# chaves.net
KiCad netlist of a schematic drawn in EAGLE
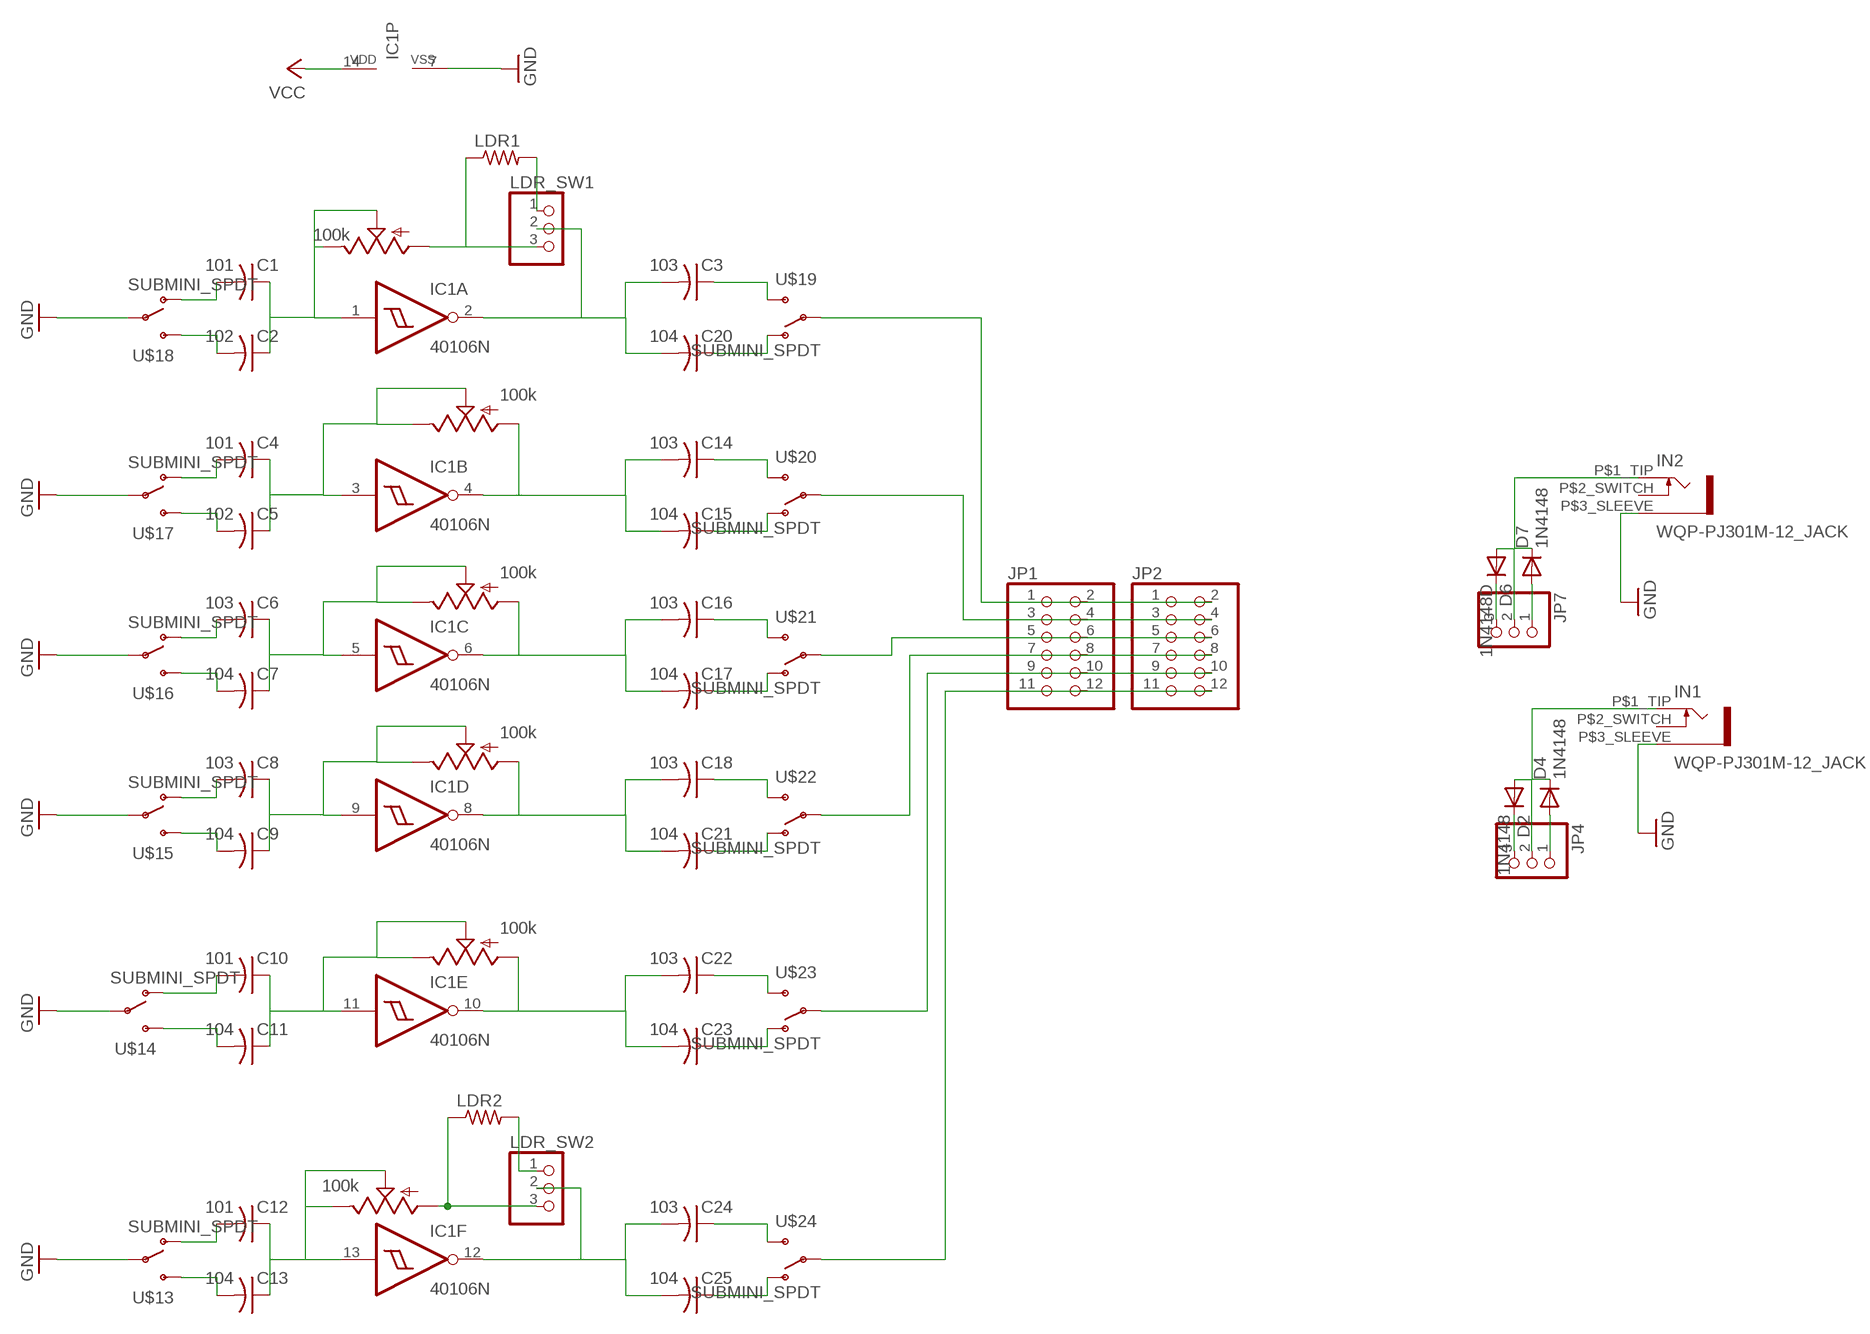
[diagram p0: schematic, sheet 1]
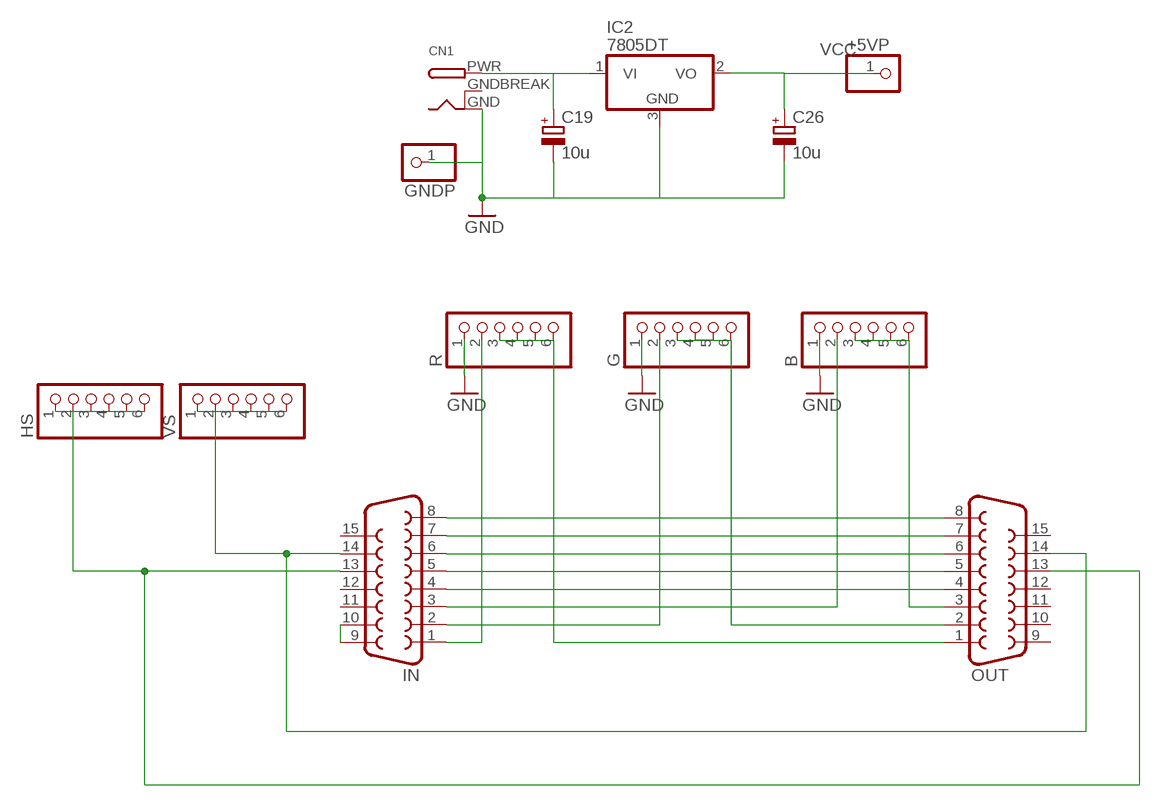
[diagram p1: schematic, sheet 2]

(export (version "E")
  (design (tool "Eeschema 10.0.6"))
  (components
    (comp (ref "+5VP")
      (value "PINHD-1X1CB")
      (footprint "eagle-import:1X01-CLEANBIG")
      (libsource (lib "eagle-import") (part "PINHD-1X1CB"))
    )
    (comp (ref "B")
      (value "PINHD-1X6CLEAN")
      (footprint "eagle-import:1X06-CLEAN")
      (libsource (lib "eagle-import") (part "PINHD-1X6CLEAN"))
    )
    (comp (ref "C19")
      (value "10u")
      (footprint "eagle-import:E2,5-5")
      (libsource (lib "eagle-import") (part "CPOL-EUE2.5-5"))
    )
    (comp (ref "C26")
      (value "10u")
      (footprint "eagle-import:E2,5-5")
      (libsource (lib "eagle-import") (part "CPOL-EUE2.5-5"))
    )
    (comp (ref "CN1")
      (value "DCBARRELPTH")
      (footprint "eagle-import:DCJACK_2MM_PTH")
      (libsource (lib "eagle-import") (part "DCBARRELPTH"))
    )
    (comp (ref "G")
      (value "PINHD-1X6CLEAN")
      (footprint "eagle-import:1X06-CLEAN")
      (libsource (lib "eagle-import") (part "PINHD-1X6CLEAN"))
    )
    (comp (ref "GNDP")
      (value "PINHD-1X1CB")
      (footprint "eagle-import:1X01-CLEANBIG")
      (libsource (lib "eagle-import") (part "PINHD-1X1CB"))
    )
    (comp (ref "HS")
      (value "PINHD-1X6CLEAN")
      (footprint "eagle-import:1X06-CLEAN")
      (libsource (lib "eagle-import") (part "PINHD-1X6CLEAN"))
    )
    (comp (ref "IC2")
      (value "7805DT")
      (footprint "eagle-import:TO252")
      (libsource (lib "eagle-import") (part "78DT05"))
    )
    (comp (ref "IN")
      (value "F15HDH")
      (footprint "eagle-import:HDF15H")
      (libsource (lib "eagle-import") (part "F15HDH"))
    )
    (comp (ref "OUT")
      (value "F15HDH")
      (footprint "eagle-import:HDF15H")
      (libsource (lib "eagle-import") (part "F15HDH"))
    )
    (comp (ref "R")
      (value "PINHD-1X6CLEAN")
      (footprint "eagle-import:1X06-CLEAN")
      (libsource (lib "eagle-import") (part "PINHD-1X6CLEAN"))
    )
    (comp (ref "VS")
      (value "PINHD-1X6CLEAN")
      (footprint "eagle-import:1X06-CLEAN")
      (libsource (lib "eagle-import") (part "PINHD-1X6CLEAN"))
    )
    (comp (ref "C1")
      (value "101")
      (footprint "eagle-import:C050-025X075")
      (libsource (lib "eagle-import") (part "C-US050-025X075"))
    )
    (comp (ref "C2")
      (value "102")
      (footprint "eagle-import:C050-025X075")
      (libsource (lib "eagle-import") (part "C-US050-025X075"))
    )
    (comp (ref "C3")
      (value "103")
      (footprint "eagle-import:C050-025X075")
      (libsource (lib "eagle-import") (part "C-US050-025X075"))
    )
    (comp (ref "C4")
      (value "101")
      (footprint "eagle-import:C050-025X075")
      (libsource (lib "eagle-import") (part "C-US050-025X075"))
    )
    (comp (ref "C5")
      (value "102")
      (footprint "eagle-import:C050-025X075")
      (libsource (lib "eagle-import") (part "C-US050-025X075"))
    )
    (comp (ref "C6")
      (value "103")
      (footprint "eagle-import:C050-025X075")
      (libsource (lib "eagle-import") (part "C-US050-025X075"))
    )
    (comp (ref "C7")
      (value "104")
      (footprint "eagle-import:C050-025X075")
      (libsource (lib "eagle-import") (part "C-US050-025X075"))
    )
    (comp (ref "C8")
      (value "103")
      (footprint "eagle-import:C050-025X075")
      (libsource (lib "eagle-import") (part "C-US050-025X075"))
    )
    (comp (ref "C9")
      (value "104")
      (footprint "eagle-import:C050-025X075")
      (libsource (lib "eagle-import") (part "C-US050-025X075"))
    )
    (comp (ref "C10")
      (value "101")
      (footprint "eagle-import:C050-025X075")
      (libsource (lib "eagle-import") (part "C-US050-025X075"))
    )
    (comp (ref "C11")
      (value "104")
      (footprint "eagle-import:C050-025X075")
      (libsource (lib "eagle-import") (part "C-US050-025X075"))
    )
    (comp (ref "C12")
      (value "101")
      (footprint "eagle-import:C050-025X075")
      (libsource (lib "eagle-import") (part "C-US050-025X075"))
    )
    (comp (ref "C13")
      (value "104")
      (footprint "eagle-import:C050-025X075")
      (libsource (lib "eagle-import") (part "C-US050-025X075"))
    )
    (comp (ref "C14")
      (value "103")
      (footprint "eagle-import:C050-025X075")
      (libsource (lib "eagle-import") (part "C-US050-025X075"))
    )
    (comp (ref "C15")
      (value "104")
      (footprint "eagle-import:C050-025X075")
      (libsource (lib "eagle-import") (part "C-US050-025X075"))
    )
    (comp (ref "C16")
      (value "103")
      (footprint "eagle-import:C050-025X075")
      (libsource (lib "eagle-import") (part "C-US050-025X075"))
    )
    (comp (ref "C17")
      (value "104")
      (footprint "eagle-import:C050-025X075")
      (libsource (lib "eagle-import") (part "C-US050-025X075"))
    )
    (comp (ref "C18")
      (value "103")
      (footprint "eagle-import:C050-025X075")
      (libsource (lib "eagle-import") (part "C-US050-025X075"))
    )
    (comp (ref "C20")
      (value "104")
      (footprint "eagle-import:C050-025X075")
      (libsource (lib "eagle-import") (part "C-US050-025X075"))
    )
    (comp (ref "C21")
      (value "104")
      (footprint "eagle-import:C050-025X075")
      (libsource (lib "eagle-import") (part "C-US050-025X075"))
    )
    (comp (ref "C22")
      (value "103")
      (footprint "eagle-import:C050-025X075")
      (libsource (lib "eagle-import") (part "C-US050-025X075"))
    )
    (comp (ref "C23")
      (value "104")
      (footprint "eagle-import:C050-025X075")
      (libsource (lib "eagle-import") (part "C-US050-025X075"))
    )
    (comp (ref "C24")
      (value "103")
      (footprint "eagle-import:C050-025X075")
      (libsource (lib "eagle-import") (part "C-US050-025X075"))
    )
    (comp (ref "C25")
      (value "104")
      (footprint "eagle-import:C050-025X075")
      (libsource (lib "eagle-import") (part "C-US050-025X075"))
    )
    (comp (ref "D2")
      (value "1N4148")
      (footprint "eagle-import:DO35-7")
      (libsource (lib "eagle-import") (part "1N4148DO35-7"))
    )
    (comp (ref "D4")
      (value "1N4148")
      (footprint "eagle-import:DO35-7")
      (libsource (lib "eagle-import") (part "1N4148DO35-7"))
    )
    (comp (ref "D6")
      (value "1N4148D")
      (footprint "eagle-import:DO35-7")
      (libsource (lib "eagle-import") (part "1N4148DO35-7"))
    )
    (comp (ref "D7")
      (value "1N4148")
      (footprint "eagle-import:DO35-7")
      (libsource (lib "eagle-import") (part "1N4148DO35-7"))
    )
    (comp (ref "IC1")
      (value "40106N")
      (footprint "eagle-import:DIL14")
      (libsource (lib "eagle-import") (part "40106N"))
    )
    (comp (ref "IN1")
      (value "WQP-PJ301M-12_JACK")
      (footprint "eagle-import:WQP-PJ301M-12_JACK")
      (libsource (lib "eagle-import") (part "WQP-PJ301M-12_JACK"))
    )
    (comp (ref "IN2")
      (value "WQP-PJ301M-12_JACK")
      (footprint "eagle-import:WQP-PJ301M-12_JACK")
      (libsource (lib "eagle-import") (part "WQP-PJ301M-12_JACK"))
    )
    (comp (ref "JP1")
      (value "PINHD-2X6")
      (footprint "eagle-import:2X06")
      (libsource (lib "eagle-import") (part "PINHD-2X6"))
    )
    (comp (ref "JP2")
      (value "PINHD-2X6")
      (footprint "eagle-import:2X06")
      (libsource (lib "eagle-import") (part "PINHD-2X6"))
    )
    (comp (ref "JP4")
      (value "PINHD-1X3CB")
      (footprint "eagle-import:1X03-CLEANBIG")
      (libsource (lib "eagle-import") (part "PINHD-1X3CB"))
    )
    (comp (ref "JP7")
      (value "PINHD-1X3CB")
      (footprint "eagle-import:1X03-CLEANBIG")
      (libsource (lib "eagle-import") (part "PINHD-1X3CB"))
    )
    (comp (ref "LDR1")
      (value "R-US_0204/7")
      (footprint "eagle-import:0204_7")
      (libsource (lib "eagle-import") (part "R-US_0204/7"))
    )
    (comp (ref "LDR2")
      (value "R-US_0204/7")
      (footprint "eagle-import:0204_7")
      (libsource (lib "eagle-import") (part "R-US_0204/7"))
    )
    (comp (ref "LDR_SW1")
      (value "PINHD-1X3")
      (footprint "eagle-import:1X03")
      (libsource (lib "eagle-import") (part "pinhead_PINHD-1X3"))
    )
    (comp (ref "LDR_SW2")
      (value "PINHD-1X3")
      (footprint "eagle-import:1X03")
      (libsource (lib "eagle-import") (part "pinhead_PINHD-1X3"))
    )
    (comp (ref "POT1")
      (value "100k")
      (footprint "eagle-import:ALPS_POT_VERTICAL")
      (libsource (lib "eagle-import") (part "POT_USVERTICAL"))
    )
    (comp (ref "POT2")
      (value "100k")
      (footprint "eagle-import:ALPS_POT_VERTICAL")
      (libsource (lib "eagle-import") (part "POT_USVERTICAL"))
    )
    (comp (ref "POT3")
      (value "100k")
      (footprint "eagle-import:ALPS_POT_VERTICAL")
      (libsource (lib "eagle-import") (part "POT_USVERTICAL"))
    )
    (comp (ref "POT4")
      (value "100k")
      (footprint "eagle-import:ALPS_POT_VERTICAL")
      (libsource (lib "eagle-import") (part "POT_USVERTICAL"))
    )
    (comp (ref "POT5")
      (value "100k")
      (footprint "eagle-import:ALPS_POT_VERTICAL")
      (libsource (lib "eagle-import") (part "POT_USVERTICAL"))
    )
    (comp (ref "POT6")
      (value "100k")
      (footprint "eagle-import:ALPS_POT_VERTICAL")
      (libsource (lib "eagle-import") (part "POT_USVERTICAL"))
    )
    (comp (ref "U$13")
      (value "SUBMINI_SPDT")
      (footprint "eagle-import:SUBMINI_TOGGLE")
      (libsource (lib "eagle-import") (part "SUBMINI_SPDT"))
    )
    (comp (ref "U$14")
      (value "SUBMINI_SPDT")
      (footprint "eagle-import:SUBMINI_TOGGLE")
      (libsource (lib "eagle-import") (part "SUBMINI_SPDT"))
    )
    (comp (ref "U$15")
      (value "SUBMINI_SPDT")
      (footprint "eagle-import:SUBMINI_TOGGLE")
      (libsource (lib "eagle-import") (part "SUBMINI_SPDT"))
    )
    (comp (ref "U$16")
      (value "SUBMINI_SPDT")
      (footprint "eagle-import:SUBMINI_TOGGLE")
      (libsource (lib "eagle-import") (part "SUBMINI_SPDT"))
    )
    (comp (ref "U$17")
      (value "SUBMINI_SPDT")
      (footprint "eagle-import:SUBMINI_TOGGLE")
      (libsource (lib "eagle-import") (part "SUBMINI_SPDT"))
    )
    (comp (ref "U$18")
      (value "SUBMINI_SPDT")
      (footprint "eagle-import:SUBMINI_TOGGLE")
      (libsource (lib "eagle-import") (part "SUBMINI_SPDT"))
    )
    (comp (ref "U$19")
      (value "SUBMINI_SPDT")
      (footprint "eagle-import:SUBMINI_TOGGLE")
      (libsource (lib "eagle-import") (part "SUBMINI_SPDT"))
    )
    (comp (ref "U$20")
      (value "SUBMINI_SPDT")
      (footprint "eagle-import:SUBMINI_TOGGLE")
      (libsource (lib "eagle-import") (part "SUBMINI_SPDT"))
    )
    (comp (ref "U$21")
      (value "SUBMINI_SPDT")
      (footprint "eagle-import:SUBMINI_TOGGLE")
      (libsource (lib "eagle-import") (part "SUBMINI_SPDT"))
    )
    (comp (ref "U$22")
      (value "SUBMINI_SPDT")
      (footprint "eagle-import:SUBMINI_TOGGLE")
      (libsource (lib "eagle-import") (part "SUBMINI_SPDT"))
    )
    (comp (ref "U$23")
      (value "SUBMINI_SPDT")
      (footprint "eagle-import:SUBMINI_TOGGLE")
      (libsource (lib "eagle-import") (part "SUBMINI_SPDT"))
    )
    (comp (ref "U$24")
      (value "SUBMINI_SPDT")
      (footprint "eagle-import:SUBMINI_TOGGLE")
      (libsource (lib "eagle-import") (part "SUBMINI_SPDT"))
    )
  )
  (nets
    (net (code "1") (name "GND") (class "Default")
      (node (ref "B") (pin "1") (pinfunction "1_1") (pintype "passive"))
      (node (ref "C19") (pin "-") (pinfunction "-_-") (pintype "passive"))
      (node (ref "C26") (pin "-") (pinfunction "-_-") (pintype "passive"))
      (node (ref "CN1") (pin "GND") (pinfunction "GND_GND") (pintype "power_in"))
      (node (ref "G") (pin "1") (pinfunction "1_1") (pintype "passive"))
      (node (ref "GNDP") (pin "1") (pinfunction "1_1") (pintype "passive"))
      (node (ref "IC1") (pin "7") (pinfunction "VSS_7") (pintype "power_in"))
      (node (ref "IC2") (pin "3") (pinfunction "GND_3") (pintype "passive"))
      (node (ref "IN") (pin "10") (pinfunction "10_10") (pintype "passive"))
      (node (ref "IN") (pin "4") (pinfunction "4_4") (pintype "passive"))
      (node (ref "IN") (pin "5") (pinfunction "5_5") (pintype "passive"))
      (node (ref "IN") (pin "6") (pinfunction "6_6") (pintype "passive"))
      (node (ref "IN") (pin "7") (pinfunction "7_7") (pintype "passive"))
      (node (ref "IN") (pin "8") (pinfunction "8_8") (pintype "passive"))
      (node (ref "IN") (pin "9") (pinfunction "9_9") (pintype "passive"))
      (node (ref "IN1") (pin "P$3_SLEEVE") (pinfunction "1_P$3_SLEEVE") (pintype "passive"))
      (node (ref "IN2") (pin "P$3_SLEEVE") (pinfunction "1_P$3_SLEEVE") (pintype "passive"))
      (node (ref "OUT") (pin "4") (pinfunction "4_4") (pintype "passive"))
      (node (ref "OUT") (pin "5") (pinfunction "5_5") (pintype "passive"))
      (node (ref "OUT") (pin "6") (pinfunction "6_6") (pintype "passive"))
      (node (ref "OUT") (pin "7") (pinfunction "7_7") (pintype "passive"))
      (node (ref "OUT") (pin "8") (pinfunction "8_8") (pintype "passive"))
      (node (ref "R") (pin "1") (pinfunction "1_1") (pintype "passive"))
      (node (ref "U$13") (pin "COM") (pinfunction "COMMON_COM") (pintype "passive"))
      (node (ref "U$14") (pin "COM") (pinfunction "COMMON_COM") (pintype "passive"))
      (node (ref "U$15") (pin "COM") (pinfunction "COMMON_COM") (pintype "passive"))
      (node (ref "U$16") (pin "COM") (pinfunction "COMMON_COM") (pintype "passive"))
      (node (ref "U$17") (pin "COM") (pinfunction "COMMON_COM") (pintype "passive"))
      (node (ref "U$18") (pin "COM") (pinfunction "COMMON_COM") (pintype "passive"))
    )
    (net (code "2") (name "GNDBREAK") (class "Default")
      (node (ref "CN1") (pin "GNDBREAK") (pinfunction "GNDBREAK_GNDBREAK") (pintype "power_in"))
    )
    (net (code "3") (name "Net-(B-Pad2)") (class "Default")
      (node (ref "B") (pin "2") (pinfunction "2_2") (pintype "passive"))
      (node (ref "IN") (pin "3") (pinfunction "3_3") (pintype "passive"))
    )
    (net (code "4") (name "Net-(B-Pad3)") (class "Default")
      (node (ref "B") (pin "3") (pinfunction "3_3") (pintype "passive"))
      (node (ref "B") (pin "4") (pinfunction "4_4") (pintype "passive"))
      (node (ref "B") (pin "5") (pinfunction "5_5") (pintype "passive"))
      (node (ref "B") (pin "6") (pinfunction "6_6") (pintype "passive"))
      (node (ref "OUT") (pin "3") (pinfunction "3_3") (pintype "passive"))
    )
    (net (code "5") (name "Net-(D2-PadC)") (class "Default")
      (node (ref "D2") (pin "C") (pinfunction "C_C") (pintype "passive"))
      (node (ref "JP4") (pin "3") (pinfunction "3_3") (pintype "passive"))
    )
    (net (code "6") (name "Net-(D4-PadA)") (class "Default")
      (node (ref "D4") (pin "A") (pinfunction "A_A") (pintype "passive"))
      (node (ref "JP4") (pin "1") (pinfunction "1_1") (pintype "passive"))
    )
    (net (code "7") (name "Net-(D6-PadC)") (class "Default")
      (node (ref "D6") (pin "C") (pinfunction "C_C") (pintype "passive"))
      (node (ref "JP7") (pin "3") (pinfunction "3_3") (pintype "passive"))
    )
    (net (code "8") (name "Net-(D7-PadA)") (class "Default")
      (node (ref "D7") (pin "A") (pinfunction "A_A") (pintype "passive"))
      (node (ref "JP7") (pin "1") (pinfunction "1_1") (pintype "passive"))
    )
    (net (code "9") (name "Net-(G-Pad2)") (class "Default")
      (node (ref "G") (pin "2") (pinfunction "2_2") (pintype "passive"))
      (node (ref "IN") (pin "2") (pinfunction "2_2") (pintype "passive"))
    )
    (net (code "10") (name "Net-(G-Pad3)") (class "Default")
      (node (ref "G") (pin "3") (pinfunction "3_3") (pintype "passive"))
      (node (ref "G") (pin "4") (pinfunction "4_4") (pintype "passive"))
      (node (ref "G") (pin "5") (pinfunction "5_5") (pintype "passive"))
      (node (ref "G") (pin "6") (pinfunction "6_6") (pintype "passive"))
      (node (ref "OUT") (pin "2") (pinfunction "2_2") (pintype "passive"))
    )
    (net (code "11") (name "Net-(HS-Pad1)") (class "Default")
      (node (ref "HS") (pin "1") (pinfunction "1_1") (pintype "passive"))
      (node (ref "HS") (pin "2") (pinfunction "2_2") (pintype "passive"))
      (node (ref "HS") (pin "3") (pinfunction "3_3") (pintype "passive"))
      (node (ref "HS") (pin "4") (pinfunction "4_4") (pintype "passive"))
      (node (ref "HS") (pin "5") (pinfunction "5_5") (pintype "passive"))
      (node (ref "HS") (pin "6") (pinfunction "6_6") (pintype "passive"))
      (node (ref "IN") (pin "13") (pinfunction "13_13") (pintype "passive"))
      (node (ref "OUT") (pin "13") (pinfunction "13_13") (pintype "passive"))
    )
    (net (code "12") (name "Net-(IC1A-I)") (class "Default")
      (node (ref "C1") (pin "1") (pinfunction "1_1") (pintype "passive"))
      (node (ref "C2") (pin "1") (pinfunction "1_1") (pintype "passive"))
      (node (ref "IC1") (pin "1") (pinfunction "I_1") (pintype "input"))
      (node (ref "POT1") (pin "P$1") (pinfunction "E_P$1") (pintype "passive"))
      (node (ref "POT1") (pin "P$2") (pinfunction "S_P$2") (pintype "passive"))
    )
    (net (code "13") (name "Net-(IC1A-O)") (class "Default")
      (node (ref "C20") (pin "2") (pinfunction "2_2") (pintype "passive"))
      (node (ref "C3") (pin "2") (pinfunction "2_2") (pintype "passive"))
      (node (ref "IC1") (pin "2") (pinfunction "O_2") (pintype "output"))
      (node (ref "LDR_SW1") (pin "2") (pinfunction "2_2") (pintype "passive"))
    )
    (net (code "14") (name "Net-(IC1B-I)") (class "Default")
      (node (ref "C4") (pin "1") (pinfunction "1_1") (pintype "passive"))
      (node (ref "C5") (pin "1") (pinfunction "1_1") (pintype "passive"))
      (node (ref "IC1") (pin "3") (pinfunction "I_3") (pintype "input"))
      (node (ref "POT2") (pin "P$1") (pinfunction "E_P$1") (pintype "passive"))
      (node (ref "POT2") (pin "P$2") (pinfunction "S_P$2") (pintype "passive"))
    )
    (net (code "15") (name "Net-(IC1B-O)") (class "Default")
      (node (ref "C14") (pin "2") (pinfunction "2_2") (pintype "passive"))
      (node (ref "C15") (pin "2") (pinfunction "2_2") (pintype "passive"))
      (node (ref "IC1") (pin "4") (pinfunction "O_4") (pintype "output"))
      (node (ref "POT2") (pin "P$3") (pinfunction "A_P$3") (pintype "passive"))
    )
    (net (code "16") (name "Net-(IC1C-I)") (class "Default")
      (node (ref "C6") (pin "1") (pinfunction "1_1") (pintype "passive"))
      (node (ref "C7") (pin "1") (pinfunction "1_1") (pintype "passive"))
      (node (ref "IC1") (pin "5") (pinfunction "I_5") (pintype "input"))
      (node (ref "POT3") (pin "P$1") (pinfunction "E_P$1") (pintype "passive"))
      (node (ref "POT3") (pin "P$2") (pinfunction "S_P$2") (pintype "passive"))
    )
    (net (code "17") (name "Net-(IC1C-O)") (class "Default")
      (node (ref "C16") (pin "2") (pinfunction "2_2") (pintype "passive"))
      (node (ref "C17") (pin "2") (pinfunction "2_2") (pintype "passive"))
      (node (ref "IC1") (pin "6") (pinfunction "O_6") (pintype "output"))
      (node (ref "POT3") (pin "P$3") (pinfunction "A_P$3") (pintype "passive"))
    )
    (net (code "18") (name "Net-(IC1D-I)") (class "Default")
      (node (ref "C8") (pin "1") (pinfunction "1_1") (pintype "passive"))
      (node (ref "C9") (pin "1") (pinfunction "1_1") (pintype "passive"))
      (node (ref "IC1") (pin "9") (pinfunction "I_9") (pintype "input"))
      (node (ref "POT4") (pin "P$1") (pinfunction "E_P$1") (pintype "passive"))
      (node (ref "POT4") (pin "P$2") (pinfunction "S_P$2") (pintype "passive"))
    )
    (net (code "19") (name "Net-(IC1D-O)") (class "Default")
      (node (ref "C18") (pin "2") (pinfunction "2_2") (pintype "passive"))
      (node (ref "C21") (pin "2") (pinfunction "2_2") (pintype "passive"))
      (node (ref "IC1") (pin "8") (pinfunction "O_8") (pintype "output"))
      (node (ref "POT4") (pin "P$3") (pinfunction "A_P$3") (pintype "passive"))
    )
    (net (code "20") (name "Net-(IC1E-I)") (class "Default")
      (node (ref "C10") (pin "1") (pinfunction "1_1") (pintype "passive"))
      (node (ref "C11") (pin "1") (pinfunction "1_1") (pintype "passive"))
      (node (ref "IC1") (pin "11") (pinfunction "I_11") (pintype "input"))
      (node (ref "POT5") (pin "P$1") (pinfunction "E_P$1") (pintype "passive"))
      (node (ref "POT5") (pin "P$2") (pinfunction "S_P$2") (pintype "passive"))
    )
    (net (code "21") (name "Net-(IC1E-O)") (class "Default")
      (node (ref "C22") (pin "2") (pinfunction "2_2") (pintype "passive"))
      (node (ref "C23") (pin "2") (pinfunction "2_2") (pintype "passive"))
      (node (ref "IC1") (pin "10") (pinfunction "O_10") (pintype "output"))
      (node (ref "POT5") (pin "P$3") (pinfunction "A_P$3") (pintype "passive"))
    )
    (net (code "22") (name "Net-(IC1F-I)") (class "Default")
      (node (ref "C12") (pin "1") (pinfunction "1_1") (pintype "passive"))
      (node (ref "C13") (pin "1") (pinfunction "1_1") (pintype "passive"))
      (node (ref "IC1") (pin "13") (pinfunction "I_13") (pintype "input"))
      (node (ref "POT6") (pin "P$1") (pinfunction "E_P$1") (pintype "passive"))
      (node (ref "POT6") (pin "P$2") (pinfunction "S_P$2") (pintype "passive"))
    )
    (net (code "23") (name "Net-(IC1F-O)") (class "Default")
      (node (ref "C24") (pin "2") (pinfunction "2_2") (pintype "passive"))
      (node (ref "C25") (pin "2") (pinfunction "2_2") (pintype "passive"))
      (node (ref "IC1") (pin "12") (pinfunction "O_12") (pintype "output"))
      (node (ref "LDR_SW2") (pin "2") (pinfunction "2_2") (pintype "passive"))
    )
    (net (code "24") (name "Net-(IC2-VI)") (class "Default")
      (node (ref "C19") (pin "+") (pinfunction "+_+") (pintype "passive"))
      (node (ref "CN1") (pin "PWR") (pinfunction "PWR_PWR") (pintype "power_in"))
      (node (ref "IC2") (pin "1") (pinfunction "VI_1") (pintype "input"))
    )
    (net (code "25") (name "Net-(IN-Pad1)") (class "Default")
      (node (ref "IN") (pin "1") (pinfunction "1_1") (pintype "passive"))
      (node (ref "R") (pin "2") (pinfunction "2_2") (pintype "passive"))
    )
    (net (code "26") (name "Net-(IN-Pad14)") (class "Default")
      (node (ref "IN") (pin "14") (pinfunction "14_14") (pintype "passive"))
      (node (ref "OUT") (pin "14") (pinfunction "14_14") (pintype "passive"))
      (node (ref "VS") (pin "1") (pinfunction "1_1") (pintype "passive"))
      (node (ref "VS") (pin "2") (pinfunction "2_2") (pintype "passive"))
      (node (ref "VS") (pin "3") (pinfunction "3_3") (pintype "passive"))
      (node (ref "VS") (pin "4") (pinfunction "4_4") (pintype "passive"))
      (node (ref "VS") (pin "5") (pinfunction "5_5") (pintype "passive"))
      (node (ref "VS") (pin "6") (pinfunction "6_6") (pintype "passive"))
    )
    (net (code "27") (name "Net-(IN1-2)") (class "Default")
      (node (ref "D2") (pin "A") (pinfunction "A_A") (pintype "passive"))
      (node (ref "D4") (pin "C") (pinfunction "C_C") (pintype "passive"))
      (node (ref "IN1") (pin "P$1_TIP") (pinfunction "2_P$1_TIP") (pintype "passive"))
      (node (ref "JP4") (pin "2") (pinfunction "2_2") (pintype "passive"))
    )
    (net (code "28") (name "Net-(IN2-2)") (class "Default")
      (node (ref "D6") (pin "A") (pinfunction "A_A") (pintype "passive"))
      (node (ref "D7") (pin "C") (pinfunction "C_C") (pintype "passive"))
      (node (ref "IN2") (pin "P$1_TIP") (pinfunction "2_P$1_TIP") (pintype "passive"))
      (node (ref "JP7") (pin "2") (pinfunction "2_2") (pintype "passive"))
    )
    (net (code "29") (name "Net-(LDR1-Pad2)") (class "Default")
      (node (ref "LDR1") (pin "2") (pinfunction "2_2") (pintype "passive"))
      (node (ref "LDR_SW1") (pin "1") (pinfunction "1_1") (pintype "passive"))
    )
    (net (code "30") (name "Net-(LDR2-Pad2)") (class "Default")
      (node (ref "LDR2") (pin "2") (pinfunction "2_2") (pintype "passive"))
      (node (ref "LDR_SW2") (pin "1") (pinfunction "1_1") (pintype "passive"))
    )
    (net (code "31") (name "Net-(OUT-Pad1)") (class "Default")
      (node (ref "OUT") (pin "1") (pinfunction "1_1") (pintype "passive"))
      (node (ref "R") (pin "3") (pinfunction "3_3") (pintype "passive"))
      (node (ref "R") (pin "4") (pinfunction "4_4") (pintype "passive"))
      (node (ref "R") (pin "5") (pinfunction "5_5") (pintype "passive"))
      (node (ref "R") (pin "6") (pinfunction "6_6") (pintype "passive"))
    )
    (net (code "32") (name "Net-(POT1-A)") (class "Default")
      (node (ref "LDR1") (pin "1") (pinfunction "1_1") (pintype "passive"))
      (node (ref "LDR_SW1") (pin "3") (pinfunction "3_3") (pintype "passive"))
      (node (ref "POT1") (pin "P$3") (pinfunction "A_P$3") (pintype "passive"))
    )
    (net (code "33") (name "Net-(POT6-A)") (class "Default")
      (node (ref "LDR2") (pin "1") (pinfunction "1_1") (pintype "passive"))
      (node (ref "LDR_SW2") (pin "3") (pinfunction "3_3") (pintype "passive"))
      (node (ref "POT6") (pin "P$3") (pinfunction "A_P$3") (pintype "passive"))
    )
    (net (code "34") (name "Net-(U$13-O)") (class "Default")
      (node (ref "C12") (pin "2") (pinfunction "2_2") (pintype "passive"))
      (node (ref "U$13") (pin "1") (pinfunction "O_1") (pintype "passive"))
    )
    (net (code "35") (name "Net-(U$13-S)") (class "Default")
      (node (ref "C13") (pin "2") (pinfunction "2_2") (pintype "passive"))
      (node (ref "U$13") (pin "3") (pinfunction "S_3") (pintype "passive"))
    )
    (net (code "36") (name "Net-(U$14-O)") (class "Default")
      (node (ref "C10") (pin "2") (pinfunction "2_2") (pintype "passive"))
      (node (ref "U$14") (pin "1") (pinfunction "O_1") (pintype "passive"))
    )
    (net (code "37") (name "Net-(U$14-S)") (class "Default")
      (node (ref "C11") (pin "2") (pinfunction "2_2") (pintype "passive"))
      (node (ref "U$14") (pin "3") (pinfunction "S_3") (pintype "passive"))
    )
    (net (code "38") (name "Net-(U$15-O)") (class "Default")
      (node (ref "C8") (pin "2") (pinfunction "2_2") (pintype "passive"))
      (node (ref "U$15") (pin "1") (pinfunction "O_1") (pintype "passive"))
    )
    (net (code "39") (name "Net-(U$15-S)") (class "Default")
      (node (ref "C9") (pin "2") (pinfunction "2_2") (pintype "passive"))
      (node (ref "U$15") (pin "3") (pinfunction "S_3") (pintype "passive"))
    )
    (net (code "40") (name "Net-(U$16-O)") (class "Default")
      (node (ref "C6") (pin "2") (pinfunction "2_2") (pintype "passive"))
      (node (ref "U$16") (pin "1") (pinfunction "O_1") (pintype "passive"))
    )
    (net (code "41") (name "Net-(U$16-S)") (class "Default")
      (node (ref "C7") (pin "2") (pinfunction "2_2") (pintype "passive"))
      (node (ref "U$16") (pin "3") (pinfunction "S_3") (pintype "passive"))
    )
    (net (code "42") (name "Net-(U$17-O)") (class "Default")
      (node (ref "C4") (pin "2") (pinfunction "2_2") (pintype "passive"))
      (node (ref "U$17") (pin "1") (pinfunction "O_1") (pintype "passive"))
    )
    (net (code "43") (name "Net-(U$17-S)") (class "Default")
      (node (ref "C5") (pin "2") (pinfunction "2_2") (pintype "passive"))
      (node (ref "U$17") (pin "3") (pinfunction "S_3") (pintype "passive"))
    )
    (net (code "44") (name "Net-(U$18-O)") (class "Default")
      (node (ref "C1") (pin "2") (pinfunction "2_2") (pintype "passive"))
      (node (ref "U$18") (pin "1") (pinfunction "O_1") (pintype "passive"))
    )
    (net (code "45") (name "Net-(U$18-S)") (class "Default")
      (node (ref "C2") (pin "2") (pinfunction "2_2") (pintype "passive"))
      (node (ref "U$18") (pin "3") (pinfunction "S_3") (pintype "passive"))
    )
    (net (code "46") (name "Net-(U$19-COMMON)") (class "Default")
      (node (ref "JP1") (pin "1") (pinfunction "1_1") (pintype "passive"))
      (node (ref "JP1") (pin "2") (pinfunction "2_2") (pintype "passive"))
      (node (ref "JP2") (pin "1") (pinfunction "1_1") (pintype "passive"))
      (node (ref "JP2") (pin "2") (pinfunction "2_2") (pintype "passive"))
      (node (ref "U$19") (pin "COM") (pinfunction "COMMON_COM") (pintype "passive"))
    )
    (net (code "47") (name "Net-(U$19-O)") (class "Default")
      (node (ref "C20") (pin "1") (pinfunction "1_1") (pintype "passive"))
      (node (ref "U$19") (pin "1") (pinfunction "O_1") (pintype "passive"))
    )
    (net (code "48") (name "Net-(U$19-S)") (class "Default")
      (node (ref "C3") (pin "1") (pinfunction "1_1") (pintype "passive"))
      (node (ref "U$19") (pin "3") (pinfunction "S_3") (pintype "passive"))
    )
    (net (code "49") (name "Net-(U$20-COMMON)") (class "Default")
      (node (ref "JP1") (pin "3") (pinfunction "3_3") (pintype "passive"))
      (node (ref "JP1") (pin "4") (pinfunction "4_4") (pintype "passive"))
      (node (ref "JP2") (pin "3") (pinfunction "3_3") (pintype "passive"))
      (node (ref "JP2") (pin "4") (pinfunction "4_4") (pintype "passive"))
      (node (ref "U$20") (pin "COM") (pinfunction "COMMON_COM") (pintype "passive"))
    )
    (net (code "50") (name "Net-(U$20-O)") (class "Default")
      (node (ref "C15") (pin "1") (pinfunction "1_1") (pintype "passive"))
      (node (ref "U$20") (pin "1") (pinfunction "O_1") (pintype "passive"))
    )
    (net (code "51") (name "Net-(U$20-S)") (class "Default")
      (node (ref "C14") (pin "1") (pinfunction "1_1") (pintype "passive"))
      (node (ref "U$20") (pin "3") (pinfunction "S_3") (pintype "passive"))
    )
    (net (code "52") (name "Net-(U$21-COMMON)") (class "Default")
      (node (ref "JP1") (pin "5") (pinfunction "5_5") (pintype "passive"))
      (node (ref "JP1") (pin "6") (pinfunction "6_6") (pintype "passive"))
      (node (ref "JP2") (pin "5") (pinfunction "5_5") (pintype "passive"))
      (node (ref "JP2") (pin "6") (pinfunction "6_6") (pintype "passive"))
      (node (ref "U$21") (pin "COM") (pinfunction "COMMON_COM") (pintype "passive"))
    )
    (net (code "53") (name "Net-(U$21-O)") (class "Default")
      (node (ref "C17") (pin "1") (pinfunction "1_1") (pintype "passive"))
      (node (ref "U$21") (pin "1") (pinfunction "O_1") (pintype "passive"))
    )
    (net (code "54") (name "Net-(U$21-S)") (class "Default")
      (node (ref "C16") (pin "1") (pinfunction "1_1") (pintype "passive"))
      (node (ref "U$21") (pin "3") (pinfunction "S_3") (pintype "passive"))
    )
    (net (code "55") (name "Net-(U$22-COMMON)") (class "Default")
      (node (ref "JP1") (pin "7") (pinfunction "7_7") (pintype "passive"))
      (node (ref "JP1") (pin "8") (pinfunction "8_8") (pintype "passive"))
      (node (ref "JP2") (pin "7") (pinfunction "7_7") (pintype "passive"))
      (node (ref "JP2") (pin "8") (pinfunction "8_8") (pintype "passive"))
      (node (ref "U$22") (pin "COM") (pinfunction "COMMON_COM") (pintype "passive"))
    )
    (net (code "56") (name "Net-(U$22-O)") (class "Default")
      (node (ref "C21") (pin "1") (pinfunction "1_1") (pintype "passive"))
      (node (ref "U$22") (pin "1") (pinfunction "O_1") (pintype "passive"))
    )
    (net (code "57") (name "Net-(U$22-S)") (class "Default")
      (node (ref "C18") (pin "1") (pinfunction "1_1") (pintype "passive"))
      (node (ref "U$22") (pin "3") (pinfunction "S_3") (pintype "passive"))
    )
    (net (code "58") (name "Net-(U$23-COMMON)") (class "Default")
      (node (ref "JP1") (pin "10") (pinfunction "10_10") (pintype "passive"))
      (node (ref "JP1") (pin "9") (pinfunction "9_9") (pintype "passive"))
      (node (ref "JP2") (pin "10") (pinfunction "10_10") (pintype "passive"))
      (node (ref "JP2") (pin "9") (pinfunction "9_9") (pintype "passive"))
      (node (ref "U$23") (pin "COM") (pinfunction "COMMON_COM") (pintype "passive"))
    )
    (net (code "59") (name "Net-(U$23-O)") (class "Default")
      (node (ref "C23") (pin "1") (pinfunction "1_1") (pintype "passive"))
      (node (ref "U$23") (pin "1") (pinfunction "O_1") (pintype "passive"))
    )
    (net (code "60") (name "Net-(U$23-S)") (class "Default")
      (node (ref "C22") (pin "1") (pinfunction "1_1") (pintype "passive"))
      (node (ref "U$23") (pin "3") (pinfunction "S_3") (pintype "passive"))
    )
    (net (code "61") (name "Net-(U$24-COMMON)") (class "Default")
      (node (ref "JP1") (pin "11") (pinfunction "11_11") (pintype "passive"))
      (node (ref "JP1") (pin "12") (pinfunction "12_12") (pintype "passive"))
      (node (ref "JP2") (pin "11") (pinfunction "11_11") (pintype "passive"))
      (node (ref "JP2") (pin "12") (pinfunction "12_12") (pintype "passive"))
      (node (ref "U$24") (pin "COM") (pinfunction "COMMON_COM") (pintype "passive"))
    )
    (net (code "62") (name "Net-(U$24-O)") (class "Default")
      (node (ref "C25") (pin "1") (pinfunction "1_1") (pintype "passive"))
      (node (ref "U$24") (pin "1") (pinfunction "O_1") (pintype "passive"))
    )
    (net (code "63") (name "Net-(U$24-S)") (class "Default")
      (node (ref "C24") (pin "1") (pinfunction "1_1") (pintype "passive"))
      (node (ref "U$24") (pin "3") (pinfunction "S_3") (pintype "passive"))
    )
    (net (code "64") (name "VCC") (class "Default")
      (node (ref "+5VP") (pin "1") (pinfunction "1_1") (pintype "passive"))
      (node (ref "C26") (pin "+") (pinfunction "+_+") (pintype "passive"))
      (node (ref "IC1") (pin "14") (pinfunction "VDD_14") (pintype "power_in"))
      (node (ref "IC2") (pin "2") (pinfunction "VO_2") (pintype "passive"))
    )
    (net (code "65") (name "unconnected-(IN-Pad11)") (class "Default")
      (node (ref "IN") (pin "11") (pinfunction "11_11") (pintype "passive"))
    )
    (net (code "66") (name "unconnected-(IN-Pad12)") (class "Default")
      (node (ref "IN") (pin "12") (pinfunction "12_12") (pintype "passive"))
    )
    (net (code "67") (name "unconnected-(IN-Pad15)") (class "Default")
      (node (ref "IN") (pin "15") (pinfunction "15_15") (pintype "passive"))
    )
    (net (code "68") (name "unconnected-(IN1-3-PadP$2_SWITCH)") (class "Default")
      (node (ref "IN1") (pin "P$2_SWITCH") (pinfunction "3_P$2_SWITCH") (pintype "passive"))
    )
    (net (code "69") (name "unconnected-(IN2-3-PadP$2_SWITCH)") (class "Default")
      (node (ref "IN2") (pin "P$2_SWITCH") (pinfunction "3_P$2_SWITCH") (pintype "passive"))
    )
    (net (code "70") (name "unconnected-(OUT-Pad9)") (class "Default")
      (node (ref "OUT") (pin "9") (pinfunction "9_9") (pintype "passive"))
    )
    (net (code "71") (name "unconnected-(OUT-Pad10)") (class "Default")
      (node (ref "OUT") (pin "10") (pinfunction "10_10") (pintype "passive"))
    )
    (net (code "72") (name "unconnected-(OUT-Pad11)") (class "Default")
      (node (ref "OUT") (pin "11") (pinfunction "11_11") (pintype "passive"))
    )
    (net (code "73") (name "unconnected-(OUT-Pad12)") (class "Default")
      (node (ref "OUT") (pin "12") (pinfunction "12_12") (pintype "passive"))
    )
    (net (code "74") (name "unconnected-(OUT-Pad15)") (class "Default")
      (node (ref "OUT") (pin "15") (pinfunction "15_15") (pintype "passive"))
    )
  )
)
